# Sheet1.net
KiCad netlist of a schematic drawn in Altium Designer
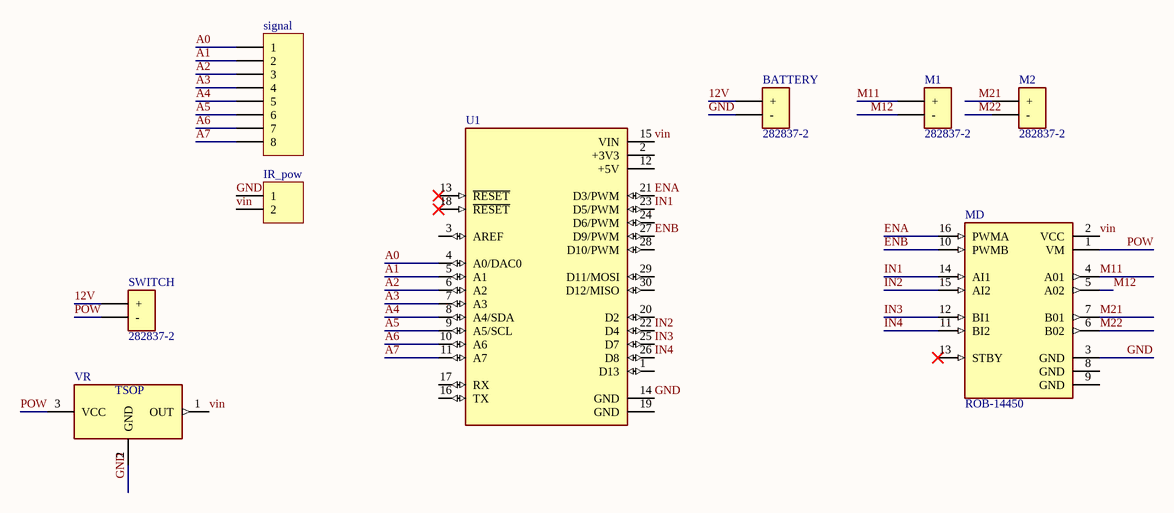
[diagram p0: Sheet1.SchDoc]

(export (version "E")
  (design (tool "Eeschema 10.0.6"))
  (components
    (comp (ref "BATTERY")
      (value "282837-2")
      (footprint "TE_282837-2")
      (fields (field (name "MF") "TE Connectivity"))
      (libsource (lib "282837-2") (part "282837-2"))
    )
    (comp (ref "IR_pow")
      (value "Header 2")
      (footprint "HDR1X2")
      (description "Header, 2-Pin")
      (fields (field (name "PUBLISHER") "Altium Limited"))
      (libsource (lib "Miscellaneous Connectors") (part "Header 2"))
    )
    (comp (ref "M1")
      (value "282837-2")
      (footprint "TE_282837-2")
      (fields (field (name "MF") "TE Connectivity"))
      (libsource (lib "282837-2") (part "282837-2"))
    )
    (comp (ref "M2")
      (value "282837-2")
      (footprint "TE_282837-2")
      (fields (field (name "MF") "TE Connectivity"))
      (libsource (lib "282837-2") (part "282837-2"))
    )
    (comp (ref "MD")
      (value "ROB-14450")
      (footprint "MODULE_ROB-14450")
      (description "TB6612FNG Motor Controller/Driver Power Management Evaluation Board")
      (fields (field (name "MF") "SparkFun Electronics"))
      (libsource (lib "ROB-14450") (part "ROB-14450"))
    )
    (comp (ref "signal")
      (value "Header 8")
      (footprint "HDR1X8")
      (description "Header, 8-Pin")
      (fields (field (name "PUBLISHER") "Altium Limited"))
      (libsource (lib "Miscellaneous Connectors") (part "Header 8"))
    )
    (comp (ref "SWITCH")
      (value "282837-2")
      (footprint "TE_282837-2")
      (fields (field (name "MF") "TE Connectivity"))
      (libsource (lib "282837-2") (part "282837-2"))
    )
    (comp (ref "U1")
      (value "ABX00028")
      (footprint "MODULE_ABX00028")
      (description "Arduinoâ€™s 5V compatible board in the smallest available form factor: 45x18mm!")
      (fields (field (name "MP") "Arduino Nano Every") (field (name "MF") "Arduino"))
      (libsource (lib "ABX00028") (part "ABX00028"))
    )
    (comp (ref "VR")
      (value "TSOP1838")
      (footprint "TSOP1838")
      (description "IR Remote Receiver 38KHz 35m 3-Pin")
      (fields (field (name "MF") "Vishay"))
      (libsource (lib "TSOP1838") (part "TSOP1838"))
    )
  )
  (nets
    (net (code "1") (name "/12V") (class "Default")
      (node (ref "BATTERY") (pin "1") (pinfunction "+_1") (pintype "passive"))
      (node (ref "SWITCH") (pin "1") (pinfunction "+_1") (pintype "passive"))
    )
    (net (code "2") (name "/A0") (class "Default")
      (node (ref "U1") (pin "4") (pinfunction "A0/DAC0_4") (pintype "bidirectional"))
      (node (ref "signal") (pin "1") (pinfunction "1_1") (pintype "passive"))
    )
    (net (code "3") (name "/A1") (class "Default")
      (node (ref "U1") (pin "5") (pinfunction "A1_5") (pintype "bidirectional"))
      (node (ref "signal") (pin "2") (pinfunction "2_2") (pintype "passive"))
    )
    (net (code "4") (name "/A2") (class "Default")
      (node (ref "U1") (pin "6") (pinfunction "A2_6") (pintype "bidirectional"))
      (node (ref "signal") (pin "3") (pinfunction "3_3") (pintype "passive"))
    )
    (net (code "5") (name "/A3") (class "Default")
      (node (ref "U1") (pin "7") (pinfunction "A3_7") (pintype "bidirectional"))
      (node (ref "signal") (pin "4") (pinfunction "4_4") (pintype "passive"))
    )
    (net (code "6") (name "/A4") (class "Default")
      (node (ref "U1") (pin "8") (pinfunction "A4/SDA_8") (pintype "bidirectional"))
      (node (ref "signal") (pin "5") (pinfunction "5_5") (pintype "passive"))
    )
    (net (code "7") (name "/A5") (class "Default")
      (node (ref "U1") (pin "9") (pinfunction "A5/SCL_9") (pintype "bidirectional"))
      (node (ref "signal") (pin "6") (pinfunction "6_6") (pintype "passive"))
    )
    (net (code "8") (name "/A6") (class "Default")
      (node (ref "U1") (pin "10") (pinfunction "A6_10") (pintype "bidirectional"))
      (node (ref "signal") (pin "7") (pinfunction "7_7") (pintype "passive"))
    )
    (net (code "9") (name "/A7") (class "Default")
      (node (ref "U1") (pin "11") (pinfunction "A7_11") (pintype "bidirectional"))
      (node (ref "signal") (pin "8") (pinfunction "8_8") (pintype "passive"))
    )
    (net (code "10") (name "/ENA") (class "Default")
      (node (ref "MD") (pin "16") (pinfunction "PWMA_16") (pintype "input"))
      (node (ref "U1") (pin "21") (pinfunction "D3/PWM_21") (pintype "bidirectional"))
    )
    (net (code "11") (name "/ENB") (class "Default")
      (node (ref "MD") (pin "10") (pinfunction "PWMB_10") (pintype "input"))
      (node (ref "U1") (pin "27") (pinfunction "D9/PWM_27") (pintype "bidirectional"))
    )
    (net (code "12") (name "/GND") (class "Default")
      (node (ref "BATTERY") (pin "2") (pinfunction "-_2") (pintype "passive"))
      (node (ref "IR_pow") (pin "1") (pinfunction "1_1") (pintype "passive"))
      (node (ref "MD") (pin "3") (pinfunction "GND_3") (pintype "power_in"))
      (node (ref "U1") (pin "14") (pinfunction "GND_14") (pintype "power_in"))
      (node (ref "VR") (pin "2") (pinfunction "GND_2") (pintype "power_in"))
    )
    (net (code "13") (name "/IN1") (class "Default")
      (node (ref "MD") (pin "14") (pinfunction "AI1_14") (pintype "input"))
      (node (ref "U1") (pin "23") (pinfunction "D5/PWM_23") (pintype "bidirectional"))
    )
    (net (code "14") (name "/IN2") (class "Default")
      (node (ref "MD") (pin "15") (pinfunction "AI2_15") (pintype "input"))
      (node (ref "U1") (pin "22") (pinfunction "D4_22") (pintype "bidirectional"))
    )
    (net (code "15") (name "/IN3") (class "Default")
      (node (ref "MD") (pin "12") (pinfunction "BI1_12") (pintype "input"))
      (node (ref "U1") (pin "25") (pinfunction "D7_25") (pintype "bidirectional"))
    )
    (net (code "16") (name "/IN4") (class "Default")
      (node (ref "MD") (pin "11") (pinfunction "BI2_11") (pintype "input"))
      (node (ref "U1") (pin "26") (pinfunction "D8_26") (pintype "bidirectional"))
    )
    (net (code "17") (name "/M11") (class "Default")
      (node (ref "M1") (pin "1") (pinfunction "+_1") (pintype "passive"))
      (node (ref "MD") (pin "4") (pinfunction "A01_4") (pintype "output"))
    )
    (net (code "18") (name "/M12") (class "Default")
      (node (ref "M1") (pin "2") (pinfunction "-_2") (pintype "passive"))
      (node (ref "MD") (pin "5") (pinfunction "A02_5") (pintype "output"))
    )
    (net (code "19") (name "/M21") (class "Default")
      (node (ref "M2") (pin "1") (pinfunction "+_1") (pintype "passive"))
      (node (ref "MD") (pin "7") (pinfunction "B01_7") (pintype "output"))
    )
    (net (code "20") (name "/M22") (class "Default")
      (node (ref "M2") (pin "2") (pinfunction "-_2") (pintype "passive"))
      (node (ref "MD") (pin "6") (pinfunction "B02_6") (pintype "output"))
    )
    (net (code "21") (name "/POW") (class "Default")
      (node (ref "MD") (pin "1") (pinfunction "VM_1") (pintype "power_in"))
      (node (ref "SWITCH") (pin "2") (pinfunction "-_2") (pintype "passive"))
      (node (ref "VR") (pin "3") (pinfunction "VCC_3") (pintype "power_in"))
    )
    (net (code "22") (name "/vin") (class "Default")
      (node (ref "IR_pow") (pin "2") (pinfunction "2_2") (pintype "passive"))
      (node (ref "MD") (pin "2") (pinfunction "VCC_2") (pintype "power_in"))
      (node (ref "U1") (pin "15") (pinfunction "VIN_15") (pintype "power_in"))
      (node (ref "VR") (pin "1") (pinfunction "OUT_1") (pintype "output"))
    )
    (net (code "23") (name "unconnected-(MD-GND-Pad8)") (class "Default")
      (node (ref "MD") (pin "8") (pinfunction "GND_8") (pintype "power_in"))
    )
    (net (code "24") (name "unconnected-(MD-GND-Pad9)") (class "Default")
      (node (ref "MD") (pin "9") (pinfunction "GND_9") (pintype "power_in"))
    )
    (net (code "25") (name "unconnected-(MD-STBY-Pad13)") (class "Default")
      (node (ref "MD") (pin "13") (pinfunction "STBY_13") (pintype "input+no_connect"))
    )
    (net (code "26") (name "unconnected-(U1-+3V3-Pad2)") (class "Default")
      (node (ref "U1") (pin "2") (pinfunction "+3V3_2") (pintype "power_in"))
    )
    (net (code "27") (name "unconnected-(U1-+5V-Pad12)") (class "Default")
      (node (ref "U1") (pin "12") (pinfunction "+5V_12") (pintype "power_in"))
    )
    (net (code "28") (name "unconnected-(U1-AREF-Pad3)") (class "Default")
      (node (ref "U1") (pin "3") (pinfunction "AREF_3") (pintype "bidirectional"))
    )
    (net (code "29") (name "unconnected-(U1-D2-Pad20)") (class "Default")
      (node (ref "U1") (pin "20") (pinfunction "D2_20") (pintype "bidirectional"))
    )
    (net (code "30") (name "unconnected-(U1-D6{slash}PWM-Pad24)") (class "Default")
      (node (ref "U1") (pin "24") (pinfunction "D6/PWM_24") (pintype "bidirectional"))
    )
    (net (code "31") (name "unconnected-(U1-D10{slash}PWM-Pad28)") (class "Default")
      (node (ref "U1") (pin "28") (pinfunction "D10/PWM_28") (pintype "bidirectional"))
    )
    (net (code "32") (name "unconnected-(U1-D11{slash}MOSI-Pad29)") (class "Default")
      (node (ref "U1") (pin "29") (pinfunction "D11/MOSI_29") (pintype "bidirectional"))
    )
    (net (code "33") (name "unconnected-(U1-D12{slash}MISO-Pad30)") (class "Default")
      (node (ref "U1") (pin "30") (pinfunction "D12/MISO_30") (pintype "bidirectional"))
    )
    (net (code "34") (name "unconnected-(U1-D13-Pad1)") (class "Default")
      (node (ref "U1") (pin "1") (pinfunction "D13_1") (pintype "bidirectional"))
    )
    (net (code "35") (name "unconnected-(U1-GND-Pad19)") (class "Default")
      (node (ref "U1") (pin "19") (pinfunction "GND_19") (pintype "power_in"))
    )
    (net (code "36") (name "unconnected-(U1-RX-Pad17)") (class "Default")
      (node (ref "U1") (pin "17") (pinfunction "RX_17") (pintype "bidirectional"))
    )
    (net (code "37") (name "unconnected-(U1-TX-Pad16)") (class "Default")
      (node (ref "U1") (pin "16") (pinfunction "TX_16") (pintype "bidirectional"))
    )
    (net (code "38") (name "unconnected-(U1-~{RESET}-Pad13)") (class "Default")
      (node (ref "U1") (pin "13") (pinfunction "~{RESET}_13") (pintype "input+no_connect"))
    )
    (net (code "39") (name "unconnected-(U1-~{RESET}-Pad18)") (class "Default")
      (node (ref "U1") (pin "18") (pinfunction "~{RESET}_18") (pintype "input+no_connect"))
    )
  )
)
